# GPRSshield_v1_4_1.net
KiCad netlist of a schematic drawn in Altium Designer
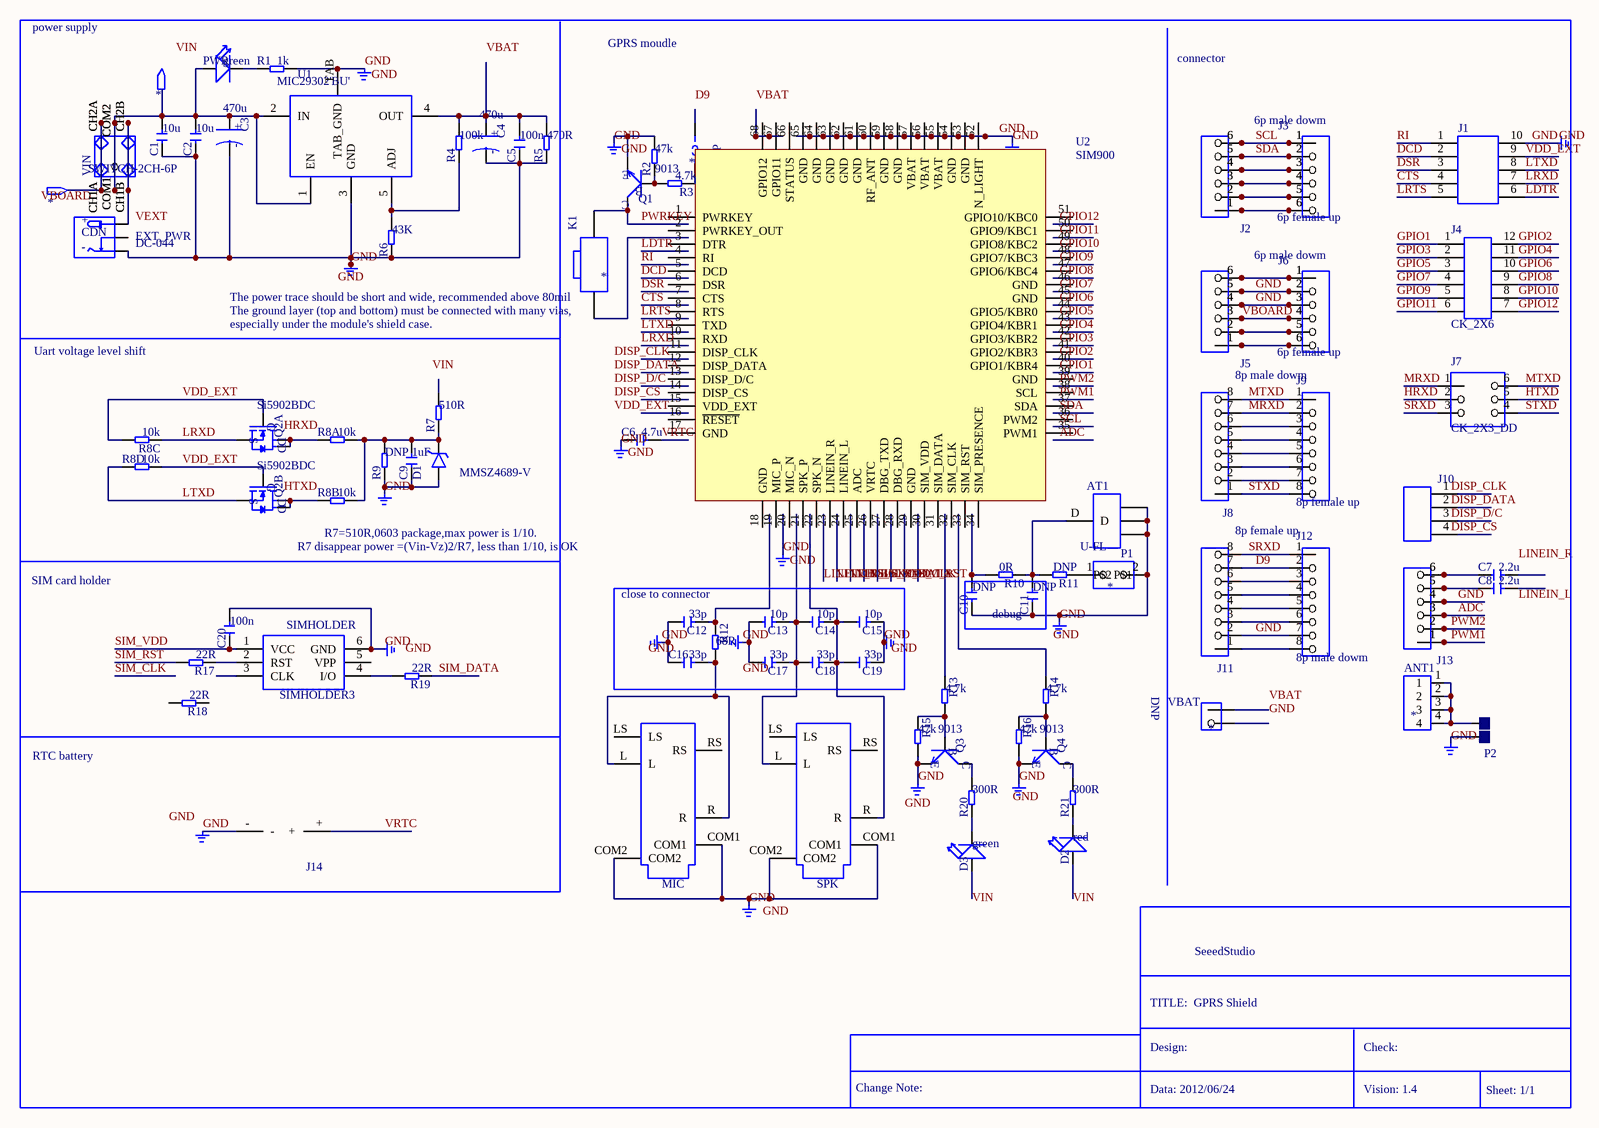
[diagram p0: GPRSshield v1.4_1.SchDoc]

(export (version "E")
  (design (tool "Eeschema 10.0.6"))
  (components
    (comp (ref "ANT1")
      (value "*")
      (footprint "SMA-TO-IPX")
      (libsource (lib "Connector") (part "ANTENNA-SMA-IPX"))
    )
    (comp (ref "AT1")
      (value "U-FL")
      (footprint "4P-U-FL")
      (libsource (lib "Connector") (part "ANTENNA-U-FL"))
    )
    (comp (ref "C1") (value "10u") (footprint "0603") (libsource (lib "Discrete") (part "C-0603")))
    (comp (ref "C2") (value "10u") (footprint "0603") (libsource (lib "Discrete") (part "C-0603")))
    (comp (ref "C3") (value "470u") (footprint "AVX_D") (libsource (lib "Discrete") (part "006-CAP_AVX_D")))
    (comp (ref "C4") (value "470u") (footprint "AVX_D") (libsource (lib "Discrete") (part "006-CAP_AVX_D")))
    (comp (ref "C5") (value "100n") (footprint "0603") (libsource (lib "Discrete") (part "C-0603")))
    (comp (ref "C6") (value "4.7u") (footprint "0805") (libsource (lib "Discrete") (part "C-0805")))
    (comp (ref "C7") (value "2.2u") (footprint "0603") (libsource (lib "Discrete") (part "C-0603")))
    (comp (ref "C8") (value "2.2u") (footprint "0603") (libsource (lib "Discrete") (part "C-0603")))
    (comp (ref "C9") (value "1uF") (footprint "0603") (libsource (lib "Discrete") (part "C-0603")))
    (comp (ref "C10") (value "DNP") (footprint "0402") (libsource (lib "") (part "C-0402_1")))
    (comp (ref "C11") (value "DNP") (footprint "0402") (libsource (lib "") (part "C-0402_1")))
    (comp (ref "C12") (value "33p") (footprint "0603") (libsource (lib "") (part "C-0603_1")))
    (comp (ref "C13") (value "10p") (footprint "0402") (libsource (lib "Discrete") (part "C-0402")))
    (comp (ref "C14") (value "10p") (footprint "0402") (libsource (lib "Discrete") (part "C-0402")))
    (comp (ref "C15") (value "10p") (footprint "0402") (libsource (lib "Discrete") (part "C-0402")))
    (comp (ref "C16") (value "33p") (footprint "0603") (libsource (lib "Discrete") (part "C-0603")))
    (comp (ref "C17") (value "33p") (footprint "0402") (libsource (lib "Discrete") (part "C-0402")))
    (comp (ref "C18") (value "33p") (footprint "0402") (libsource (lib "Discrete") (part "C-0402")))
    (comp (ref "C19") (value "33p") (footprint "0402") (libsource (lib "Discrete") (part "C-0402")))
    (comp (ref "C20") (value "100n") (footprint "0603") (libsource (lib "Discrete") (part "C-0603")))
    (comp (ref "D1")
      (value "MMSZ4689-V")
      (footprint "SOD123-2.7X1.6")
      (libsource (lib "template") (part "D-VOL'MMSZ4681'"))
    )
    (comp (ref "D2") (value "red") (footprint "LED-0603") (libsource (lib "Discrete") (part "LED'0603'")))
    (comp (ref "D3") (value "green") (footprint "LED-0603") (libsource (lib "Discrete") (part "LED'0603'")))
    (comp (ref "EXT_PWR") (value "DC-044") (footprint "DC-404") (libsource (lib "Connector") (part "DC-044")))
    (comp (ref "J1")
      (value "~")
      (footprint "2X5P-2.54")
      (libsource (lib "Connector") (part "HEADER-2X5P-2.54"))
    )
    (comp (ref "J2")
      (value "6p male dowm")
      (footprint "CK_1X6")
      (libsource (lib "CONNECTER") (part "HEADER_1X6"))
    )
    (comp (ref "J3")
      (value "6p female up")
      (footprint "CK_1X6")
      (libsource (lib "CONNECTER") (part "HEADER_1X6"))
    )
    (comp (ref "J4") (value "CK_2X6") (footprint "CK_2X6") (libsource (lib "CONNECTER") (part "CK_2X6")))
    (comp (ref "J5")
      (value "6p male dowm")
      (footprint "CK_1X6")
      (libsource (lib "CONNECTER") (part "HEADER_1X6"))
    )
    (comp (ref "J6")
      (value "6p female up")
      (footprint "CK_1X6")
      (libsource (lib "CONNECTER") (part "HEADER_1X6"))
    )
    (comp (ref "J7")
      (value "CK_2X3_DD")
      (footprint "CK_2X3")
      (libsource (lib "CONNECTER") (part "CK_2X3_DD"))
    )
    (comp (ref "J8")
      (value "8p male dowm")
      (footprint "CK_1X8")
      (libsource (lib "CONNECTER") (part "CK_1X8DD"))
    )
    (comp (ref "J9")
      (value "8p female up")
      (footprint "CK_1X8")
      (libsource (lib "CONNECTER") (part "CK_1X8DD"))
    )
    (comp (ref "J10")
      (value "~")
      (footprint "4P-2.54-90D-FEMALE")
      (libsource (lib "Connector") (part "HEADER-4P'2.54-90D-FEMALE'"))
    )
    (comp (ref "J11")
      (value "8p female up")
      (footprint "CK_1X8")
      (libsource (lib "CONNECTER") (part "CK_1X8DD"))
    )
    (comp (ref "J12")
      (value "8p male dowm")
      (footprint "CK_1X8")
      (libsource (lib "CONNECTER") (part "CK_1X8DD"))
    )
    (comp (ref "J13") (value "~") (footprint "CK_1X6") (libsource (lib "CONNECTER") (part "HEADER_1X6")))
    (comp (ref "J14")
      (value "~")
      (footprint "CR1220")
      (libsource (lib "Connector") (part "HOLDER-BATTERY-2P-CR1220"))
    )
    (comp (ref "JP")
      (value "*")
      (footprint "2P-SMD-3.3X2")
      (libsource (lib "Discrete") (part "PAD-SOLDERJUMPERNC"))
    )
    (comp (ref "K1") (value "*") (footprint "BTN_5.0_RST") (libsource (lib "CPT_SMD") (part "BOTTON_1_DP")))
    (comp (ref "MIC") (value "~") (footprint "3.5-SMD") (libsource (lib "Connector") (part "AUDIO-SMT")))
    (comp (ref "P1") (value "*") (footprint "JP") (libsource (lib "mySeeed") (part "JP")))
    (comp (ref "P2")
      (value "*")
      (footprint "2P-SMD-1.78X1.27")
      (libsource (lib "Discrete") (part "PAD-JUMPER-2P"))
    )
    (comp (ref "PWR") (value "green") (footprint "D0603") (libsource (lib "Discrete") (part "007-LED0603")))
    (comp (ref "Q1")
      (value "9013")
      (footprint "SOT23")
      (libsource (lib "Discrete") (part "TRANSISTOR-NPN-SOT23"))
    )
    (comp (ref "Q2")
      (value "Si5902BDC")
      (footprint "1206-8")
      (libsource (lib "Discrete") (part "010-DUAL-N-MOSFET_1206-8"))
    )
    (comp (ref "Q3") (value "9013") (footprint "SOT23") (libsource (lib "") (part "TRANSISTOR-NPN-SOT23_1")))
    (comp (ref "Q4") (value "9013") (footprint "SOT23") (libsource (lib "") (part "TRANSISTOR-NPN-SOT23_1")))
    (comp (ref "R1") (value "1k") (footprint "0603") (libsource (lib "Discrete") (part "R-0603")))
    (comp (ref "R2") (value "47k") (footprint "0603") (libsource (lib "Discrete") (part "R-0603")))
    (comp (ref "R3") (value "4.7k") (footprint "0603") (libsource (lib "Discrete") (part "R-0603")))
    (comp (ref "R4") (value "100k") (footprint "0603") (libsource (lib "Discrete") (part "R-0603")))
    (comp (ref "R5") (value "470R") (footprint "0603") (libsource (lib "Discrete") (part "R-0603")))
    (comp (ref "R6") (value "43K") (footprint "0603") (libsource (lib "Discrete") (part "R-0603")))
    (comp (ref "R7") (value "510R") (footprint "0603") (libsource (lib "Discrete") (part "R-0603")))
    (comp (ref "R8") (value "10k") (footprint "1206-8-3.3X2.4") (libsource (lib "") (part "R-4R-1206_2")))
    (comp (ref "R9") (value "DNP") (footprint "0603") (libsource (lib "Discrete") (part "R-0603")))
    (comp (ref "R10") (value "0R") (footprint "0402") (libsource (lib "Discrete") (part "R-0402")))
    (comp (ref "R11") (value "DNP") (footprint "0402") (libsource (lib "Discrete") (part "R-0402")))
    (comp (ref "R12") (value "68R") (footprint "0603") (libsource (lib "Discrete") (part "R-0603")))
    (comp (ref "R13") (value "4.7k") (footprint "0603") (libsource (lib "Discrete") (part "R-0603")))
    (comp (ref "R14") (value "4.7k") (footprint "0603") (libsource (lib "Discrete") (part "R-0603")))
    (comp (ref "R15") (value "47k") (footprint "0603") (libsource (lib "Discrete") (part "R-0603")))
    (comp (ref "R16") (value "47k") (footprint "0603") (libsource (lib "Discrete") (part "R-0603")))
    (comp (ref "R17") (value "22R") (footprint "0603") (libsource (lib "Discrete") (part "R-0603")))
    (comp (ref "R18") (value "22R") (footprint "0603") (libsource (lib "Discrete") (part "R-0603")))
    (comp (ref "R19") (value "22R") (footprint "0603") (libsource (lib "Discrete") (part "R-0603")))
    (comp (ref "R20") (value "300R") (footprint "0603") (libsource (lib "Discrete") (part "R-0603")))
    (comp (ref "R21") (value "300R") (footprint "0603") (libsource (lib "Discrete") (part "R-0603")))
    (comp (ref "SIMHOLDER")
      (value "SIMHOLDER3")
      (footprint "SIMHOLDER3")
      (libsource (lib "SparkFun2") (part "SIMHOLDER3"))
    )
    (comp (ref "SPK") (value "~") (footprint "3.5-SMD") (libsource (lib "Connector") (part "AUDIO-SMT")))
    (comp (ref "U$1") (value "*") (libsource (lib "") (part "SINGLE-PIN_1")))
    (comp (ref "U$2") (value "~") (libsource (lib "Power or GND") (part "GND_POWER")))
    (comp (ref "U$3") (value "~") (libsource (lib "") (part "GND_POWER_1")))
    (comp (ref "U$4") (value "~") (libsource (lib "Power or GND") (part "GND_POWER")))
    (comp (ref "U$5") (value "~") (libsource (lib "Power or GND") (part "GND_POWER")))
    (comp (ref "U$6") (value "~") (libsource (lib "Power or GND") (part "GND_POWER")))
    (comp (ref "U$7") (value "~") (libsource (lib "Power or GND") (part "GND_POWER")))
    (comp (ref "U$8") (value "~") (libsource (lib "") (part "GND_POWER_1")))
    (comp (ref "U$12") (value "~") (libsource (lib "Power or GND") (part "GND_POWER")))
    (comp (ref "U$13") (value "~") (libsource (lib "Power or GND") (part "GND_POWER")))
    (comp (ref "U$14") (value "~") (libsource (lib "") (part "GND_POWER_2")))
    (comp (ref "U$15") (value "~") (libsource (lib "") (part "GND_POWER_1")))
    (comp (ref "U$16") (value "~") (libsource (lib "Power or GND") (part "GND_POWER")))
    (comp (ref "U$17") (value "~") (libsource (lib "Power or GND") (part "GND_POWER")))
    (comp (ref "U$18") (value "~") (libsource (lib "Power or GND") (part "GND_POWER")))
    (comp (ref "U$19") (value "~") (libsource (lib "Power or GND") (part "GND_POWER")))
    (comp (ref "U$20") (value "~") (libsource (lib "") (part "GND_POWER_2")))
    (comp (ref "U$21") (value "~") (libsource (lib "Power or GND") (part "GND_POWER")))
    (comp (ref "U$22") (value "~") (libsource (lib "Power or GND") (part "GND_POWER")))
    (comp (ref "U$23") (value "*") (libsource (lib "Power or GND") (part "SINGLE-PIN")))
    (comp (ref "U1")
      (value "MIC29302'BU'")
      (footprint "TO-263")
      (libsource (lib "ICs_v54") (part "MIC29302'BU'"))
    )
    (comp (ref "U2") (value "SIM900") (footprint "SIM900") (libsource (lib "SIM900") (part "SIM900")))
    (comp (ref "VBAT")
      (value "*")
      (footprint "CK_1*2")
      (libsource (lib "CONNECTER") (part "HEADER_1X2_2.54"))
    )
    (comp (ref "VIN")
      (value "SWITCH-2CH-6P")
      (footprint "6P-2CH-2.54-7.6X3.0")
      (libsource (lib "Discrete") (part "SWITCH-2CH-6P"))
    )
  )
  (nets
    (net (code "1") (name "/ADC") (class "Default")
      (node (ref "J13") (pin "3") (pinfunction "3_3") (pintype "passive"))
    )
    (net (code "2") (name "/CTS") (class "Default")
      (node (ref "J1") (pin "4") (pinfunction "4_4") (pintype "passive"))
    )
    (net (code "3") (name "/D9") (class "Default")
      (node (ref "J11") (pin "7") (pinfunction "P$7_7") (pintype "passive"))
      (node (ref "J12") (pin "2") (pinfunction "P$2_2") (pintype "passive"))
    )
    (net (code "4") (name "/DCD") (class "Default")
      (node (ref "J1") (pin "2") (pinfunction "2_2") (pintype "passive"))
    )
    (net (code "9") (name "/DSR") (class "Default")
      (node (ref "J1") (pin "3") (pinfunction "3_3") (pintype "passive"))
    )
    (net (code "10") (name "/GND") (class "Default")
      (node (ref "AT1") (pin "GND1") (pinfunction "GND1_GND1") (pintype "passive"))
      (node (ref "AT1") (pin "GND2") (pinfunction "GND2_GND2") (pintype "passive"))
      (node (ref "AT1") (pin "GND3") (pinfunction "GND3_GND3") (pintype "passive"))
      (node (ref "C1") (pin "1") (pinfunction "1_1") (pintype "passive"))
      (node (ref "C10") (pin "1") (pinfunction "1_1") (pintype "passive"))
      (node (ref "C11") (pin "1") (pinfunction "1_1") (pintype "passive"))
      (node (ref "C12") (pin "2") (pinfunction "2_2") (pintype "passive"))
      (node (ref "C13") (pin "2") (pinfunction "2_2") (pintype "passive"))
      (node (ref "C15") (pin "1") (pinfunction "1_1") (pintype "passive"))
      (node (ref "C16") (pin "1") (pinfunction "1_1") (pintype "passive"))
      (node (ref "C17") (pin "2") (pinfunction "2_2") (pintype "passive"))
      (node (ref "C19") (pin "1") (pinfunction "1_1") (pintype "passive"))
      (node (ref "C2") (pin "1") (pinfunction "1_1") (pintype "passive"))
      (node (ref "C20") (pin "2") (pinfunction "2_2") (pintype "passive"))
      (node (ref "C3") (pin "-") (pinfunction "-_-") (pintype "passive"))
      (node (ref "C4") (pin "-") (pinfunction "-_-") (pintype "passive"))
      (node (ref "C5") (pin "1") (pinfunction "1_1") (pintype "passive"))
      (node (ref "C6") (pin "1") (pinfunction "1_1") (pintype "passive"))
      (node (ref "C9") (pin "1") (pinfunction "1_1") (pintype "passive"))
      (node (ref "D1") (pin "1") (pinfunction "1_1") (pintype "passive"))
      (node (ref "EXT_PWR") (pin "-") (pinfunction "-_-") (pintype "passive"))
      (node (ref "J1") (pin "10") (pinfunction "10_10") (pintype "passive"))
      (node (ref "J11") (pin "2") (pinfunction "P$2_2") (pintype "passive"))
      (node (ref "J12") (pin "7") (pinfunction "P$7_7") (pintype "passive"))
      (node (ref "J13") (pin "4") (pinfunction "4_4") (pintype "passive"))
      (node (ref "J14") (pin "-") (pinfunction "-_-") (pintype "passive"))
      (node (ref "J5") (pin "4") (pinfunction "4_4") (pintype "passive"))
      (node (ref "J5") (pin "5") (pinfunction "5_5") (pintype "passive"))
      (node (ref "J6") (pin "2") (pinfunction "2_2") (pintype "passive"))
      (node (ref "J6") (pin "3") (pinfunction "3_3") (pintype "passive"))
      (node (ref "MIC") (pin "COM1") (pinfunction "COM1_COM1") (pintype "passive"))
      (node (ref "MIC") (pin "COM2") (pinfunction "COM2_COM2") (pintype "passive"))
      (node (ref "P1") (pin "2") (pinfunction "P$2_2") (pintype "passive"))
      (node (ref "P2") (pin "2") (pinfunction "2_2") (pintype "passive"))
      (node (ref "Q1") (pin "2") (pinfunction "E_2") (pintype "passive"))
      (node (ref "Q3") (pin "2") (pinfunction "E_2") (pintype "passive"))
      (node (ref "Q4") (pin "2") (pinfunction "E_2") (pintype "passive"))
      (node (ref "R1") (pin "2") (pinfunction "2_2") (pintype "passive"))
      (node (ref "R15") (pin "2") (pinfunction "2_2") (pintype "passive"))
      (node (ref "R16") (pin "2") (pinfunction "2_2") (pintype "passive"))
      (node (ref "R2") (pin "2") (pinfunction "2_2") (pintype "passive"))
      (node (ref "R5") (pin "1") (pinfunction "1_1") (pintype "passive"))
      (node (ref "R6") (pin "1") (pinfunction "1_1") (pintype "passive"))
      (node (ref "R9") (pin "1") (pinfunction "1_1") (pintype "passive"))
      (node (ref "SIMHOLDER") (pin "6") (pinfunction "GND_6") (pintype "passive"))
      (node (ref "SPK") (pin "COM1") (pinfunction "COM1_COM1") (pintype "passive"))
      (node (ref "SPK") (pin "COM2") (pinfunction "COM2_COM2") (pintype "passive"))
      (node (ref "U$12") (pin "0") (pinfunction "GND_0") (pintype "passive"))
      (node (ref "U$13") (pin "0") (pinfunction "GND_0") (pintype "passive"))
      (node (ref "U$14") (pin "0") (pinfunction "GND_0") (pintype "passive"))
      (node (ref "U$15") (pin "0") (pinfunction "GND_0") (pintype "passive"))
      (node (ref "U$16") (pin "0") (pinfunction "GND_0") (pintype "passive"))
      (node (ref "U$17") (pin "0") (pinfunction "GND_0") (pintype "passive"))
      (node (ref "U$18") (pin "0") (pinfunction "GND_0") (pintype "passive"))
      (node (ref "U$19") (pin "0") (pinfunction "GND_0") (pintype "passive"))
      (node (ref "U$2") (pin "0") (pinfunction "GND_0") (pintype "passive"))
      (node (ref "U$20") (pin "0") (pinfunction "GND_0") (pintype "passive"))
      (node (ref "U$21") (pin "0") (pinfunction "GND_0") (pintype "passive"))
      (node (ref "U$22") (pin "0") (pinfunction "GND_0") (pintype "passive"))
      (node (ref "U$3") (pin "0") (pinfunction "GND_0") (pintype "passive"))
      (node (ref "U$4") (pin "0") (pinfunction "GND_0") (pintype "passive"))
      (node (ref "U$5") (pin "0") (pinfunction "GND_0") (pintype "passive"))
      (node (ref "U$6") (pin "0") (pinfunction "GND_0") (pintype "passive"))
      (node (ref "U$7") (pin "0") (pinfunction "GND_0") (pintype "passive"))
      (node (ref "U$8") (pin "0") (pinfunction "GND_0") (pintype "passive"))
      (node (ref "U1") (pin "3") (pinfunction "GND_3") (pintype "passive"))
      (node (ref "U1") (pin "TAB") (pinfunction "TAB_GND_TAB") (pintype "passive"))
    )
    (net (code "11") (name "/GPIO1") (class "Default")
      (node (ref "J4") (pin "1") (pinfunction "1_1") (pintype "passive"))
    )
    (net (code "12") (name "/GPIO2") (class "Default")
      (node (ref "J4") (pin "12") (pinfunction "12_12") (pintype "passive"))
    )
    (net (code "13") (name "/GPIO3") (class "Default")
      (node (ref "J4") (pin "2") (pinfunction "2_2") (pintype "passive"))
    )
    (net (code "14") (name "/GPIO4") (class "Default")
      (node (ref "J4") (pin "11") (pinfunction "11_11") (pintype "passive"))
    )
    (net (code "15") (name "/GPIO5") (class "Default")
      (node (ref "J4") (pin "3") (pinfunction "3_3") (pintype "passive"))
    )
    (net (code "16") (name "/GPIO6") (class "Default")
      (node (ref "J4") (pin "10") (pinfunction "10_10") (pintype "passive"))
    )
    (net (code "17") (name "/GPIO7") (class "Default")
      (node (ref "J4") (pin "4") (pinfunction "4_4") (pintype "passive"))
    )
    (net (code "18") (name "/GPIO8") (class "Default")
      (node (ref "J4") (pin "9") (pinfunction "9_9") (pintype "passive"))
    )
    (net (code "19") (name "/GPIO9") (class "Default")
      (node (ref "J4") (pin "5") (pinfunction "5_5") (pintype "passive"))
    )
    (net (code "20") (name "/GPIO10") (class "Default")
      (node (ref "J4") (pin "8") (pinfunction "8_8") (pintype "passive"))
    )
    (net (code "21") (name "/GPIO11") (class "Default")
      (node (ref "J4") (pin "6") (pinfunction "6_6") (pintype "passive"))
    )
    (net (code "22") (name "/GPIO12") (class "Default")
      (node (ref "J4") (pin "7") (pinfunction "7_7") (pintype "passive"))
    )
    (net (code "23") (name "/HRXD") (class "Default")
      (node (ref "J7") (pin "2") (pinfunction "2_2") (pintype "passive"))
    )
    (net (code "24") (name "/HTXD") (class "Default")
      (node (ref "J7") (pin "5") (pinfunction "5_5") (pintype "passive"))
    )
    (net (code "27") (name "/LDTR") (class "Default")
      (node (ref "J1") (pin "6") (pinfunction "6_6") (pintype "passive"))
    )
    (net (code "30") (name "/LRTS") (class "Default")
      (node (ref "J1") (pin "5") (pinfunction "5_5") (pintype "passive"))
    )
    (net (code "31") (name "/LRXD") (class "Default")
      (node (ref "J1") (pin "7") (pinfunction "7_7") (pintype "passive"))
      (node (ref "Q2") (pin "1") (pinfunction "S_1") (pintype "passive"))
      (node (ref "R8") (pin "3") (pinfunction "1_3") (pintype "passive"))
    )
    (net (code "32") (name "/LTXD") (class "Default")
      (node (ref "J1") (pin "8") (pinfunction "8_8") (pintype "passive"))
      (node (ref "Q2") (pin "3") (pinfunction "S_3") (pintype "passive"))
      (node (ref "R8") (pin "4") (pinfunction "1_4") (pintype "passive"))
    )
    (net (code "33") (name "/MRXD") (class "Default")
      (node (ref "J7") (pin "1") (pinfunction "1_1") (pintype "passive"))
      (node (ref "J8") (pin "7") (pinfunction "P$7_7") (pintype "passive"))
      (node (ref "J9") (pin "2") (pinfunction "P$2_2") (pintype "passive"))
    )
    (net (code "34") (name "/MTXD") (class "Default")
      (node (ref "J7") (pin "6") (pinfunction "6_6") (pintype "passive"))
      (node (ref "J8") (pin "8") (pinfunction "P$8_8") (pintype "passive"))
      (node (ref "J9") (pin "1") (pinfunction "P$1_1") (pintype "passive"))
    )
    (net (code "35") (name "/PWM1") (class "Default")
      (node (ref "J13") (pin "1") (pinfunction "1_1") (pintype "passive"))
    )
    (net (code "36") (name "/PWM2") (class "Default")
      (node (ref "J13") (pin "2") (pinfunction "2_2") (pintype "passive"))
    )
    (net (code "37") (name "/PWRKEY") (class "Default")
      (node (ref "K1") (pin "P$2") (pinfunction "2_P$2") (pintype "passive"))
      (node (ref "Q1") (pin "3") (pinfunction "C_3") (pintype "passive"))
    )
    (net (code "38") (name "/RI") (class "Default")
      (node (ref "J1") (pin "1") (pinfunction "1_1") (pintype "passive"))
    )
    (net (code "39") (name "/SCL") (class "Default")
      (node (ref "J2") (pin "6") (pinfunction "6_6") (pintype "passive"))
      (node (ref "J3") (pin "1") (pinfunction "1_1") (pintype "passive"))
    )
    (net (code "40") (name "/SDA") (class "Default")
      (node (ref "J2") (pin "5") (pinfunction "5_5") (pintype "passive"))
      (node (ref "J3") (pin "2") (pinfunction "2_2") (pintype "passive"))
    )
    (net (code "42") (name "/SIM_DATA") (class "Default")
      (node (ref "R19") (pin "1") (pinfunction "1_1") (pintype "passive"))
    )
    (net (code "43") (name "/SIM_RST") (class "Default")
      (node (ref "R17") (pin "2") (pinfunction "2_2") (pintype "passive"))
    )
    (net (code "44") (name "/SIM_VDD") (class "Default")
      (node (ref "C20") (pin "1") (pinfunction "1_1") (pintype "passive"))
      (node (ref "SIMHOLDER") (pin "1") (pinfunction "VCC_1") (pintype "passive"))
    )
    (net (code "45") (name "/SRXD") (class "Default")
      (node (ref "J11") (pin "8") (pinfunction "P$8_8") (pintype "passive"))
      (node (ref "J12") (pin "1") (pinfunction "P$1_1") (pintype "passive"))
      (node (ref "J7") (pin "3") (pinfunction "3_3") (pintype "passive"))
    )
    (net (code "46") (name "/STXD") (class "Default")
      (node (ref "J7") (pin "4") (pinfunction "4_4") (pintype "passive"))
      (node (ref "J8") (pin "1") (pinfunction "P$1_1") (pintype "passive"))
      (node (ref "J9") (pin "8") (pinfunction "P$8_8") (pintype "passive"))
    )
    (net (code "48") (name "/VBOARD") (class "Default")
      (node (ref "J5") (pin "3") (pinfunction "3_3") (pintype "passive"))
      (node (ref "J6") (pin "4") (pinfunction "4_4") (pintype "passive"))
    )
    (net (code "49") (name "/VDD_EXT") (class "Default")
      (node (ref "J1") (pin "9") (pinfunction "9_9") (pintype "passive"))
      (node (ref "Q2") (pin "2") (pinfunction "G_2") (pintype "passive"))
      (node (ref "Q2") (pin "4") (pinfunction "G_4") (pintype "passive"))
      (node (ref "R8") (pin "5") (pinfunction "2_5") (pintype "passive"))
      (node (ref "R8") (pin "6") (pinfunction "2_6") (pintype "passive"))
    )
    (net (code "52") (name "/VRTC") (class "Default")
      (node (ref "C6") (pin "2") (pinfunction "2_2") (pintype "passive"))
      (node (ref "J14") (pin "+") (pinfunction "+_+") (pintype "passive"))
    )
    (net (code "53") (name "Net-(ANT1-Pad1)") (class "Default")
      (node (ref "ANT1") (pin "1") (pinfunction "1_1") (pintype "passive"))
      (node (ref "ANT1") (pin "2") (pinfunction "2_2") (pintype "passive"))
      (node (ref "ANT1") (pin "3") (pinfunction "3_3") (pintype "passive"))
      (node (ref "ANT1") (pin "4") (pinfunction "4_4") (pintype "passive"))
      (node (ref "P2") (pin "1") (pinfunction "1_1") (pintype "passive"))
    )
    (net (code "54") (name "Net-(AT1-PadD)") (class "Default")
      (node (ref "AT1") (pin "D") (pinfunction "D_D") (pintype "passive"))
      (node (ref "C11") (pin "2") (pinfunction "2_2") (pintype "passive"))
      (node (ref "R10") (pin "1") (pinfunction "1_1") (pintype "passive"))
      (node (ref "R11") (pin "2") (pinfunction "2_2") (pintype "passive"))
    )
    (net (code "55") (name "Net-(C7-Pad1)") (class "Default")
      (node (ref "C7") (pin "1") (pinfunction "1_1") (pintype "passive"))
      (node (ref "J13") (pin "6") (pinfunction "6_6") (pintype "passive"))
    )
    (net (code "56") (name "Net-(C8-Pad1)") (class "Default")
      (node (ref "C8") (pin "1") (pinfunction "1_1") (pintype "passive"))
      (node (ref "J13") (pin "5") (pinfunction "5_5") (pintype "passive"))
    )
    (net (code "57") (name "Net-(C10-Pad2)") (class "Default")
      (node (ref "C10") (pin "2") (pinfunction "2_2") (pintype "passive"))
      (node (ref "R10") (pin "2") (pinfunction "2_2") (pintype "passive"))
    )
    (net (code "58") (name "Net-(C12-Pad1)") (class "Default")
      (node (ref "C12") (pin "1") (pinfunction "1_1") (pintype "passive"))
      (node (ref "R12") (pin "1") (pinfunction "1_1") (pintype "passive"))
    )
    (net (code "59") (name "Net-(C13-Pad1)") (class "Default")
      (node (ref "C13") (pin "1") (pinfunction "1_1") (pintype "passive"))
      (node (ref "C14") (pin "2") (pinfunction "2_2") (pintype "passive"))
      (node (ref "C17") (pin "1") (pinfunction "1_1") (pintype "passive"))
      (node (ref "C18") (pin "2") (pinfunction "2_2") (pintype "passive"))
      (node (ref "SPK") (pin "L") (pinfunction "L_L") (pintype "passive"))
    )
    (net (code "60") (name "Net-(C14-Pad1)") (class "Default")
      (node (ref "C14") (pin "1") (pinfunction "1_1") (pintype "passive"))
      (node (ref "C15") (pin "2") (pinfunction "2_2") (pintype "passive"))
      (node (ref "C18") (pin "1") (pinfunction "1_1") (pintype "passive"))
      (node (ref "C19") (pin "2") (pinfunction "2_2") (pintype "passive"))
      (node (ref "SPK") (pin "R") (pinfunction "R_R") (pintype "passive"))
    )
    (net (code "61") (name "Net-(C16-Pad2)") (class "Default")
      (node (ref "C16") (pin "2") (pinfunction "2_2") (pintype "passive"))
      (node (ref "MIC") (pin "L") (pinfunction "L_L") (pintype "passive"))
      (node (ref "MIC") (pin "R") (pinfunction "R_R") (pintype "passive"))
      (node (ref "R12") (pin "2") (pinfunction "2_2") (pintype "passive"))
    )
    (net (code "62") (name "Net-(D2-Pad-)") (class "Default")
      (node (ref "D2") (pin "-") (pinfunction "-_-") (pintype "passive"))
      (node (ref "R21") (pin "1") (pinfunction "1_1") (pintype "passive"))
    )
    (net (code "63") (name "Net-(D3-Pad-)") (class "Default")
      (node (ref "D3") (pin "-") (pinfunction "-_-") (pintype "passive"))
      (node (ref "R20") (pin "1") (pinfunction "1_1") (pintype "passive"))
    )
    (net (code "64") (name "Net-(EXT_PWR-Pad+)") (class "Default")
      (node (ref "EXT_PWR") (pin "+") (pinfunction "+_+") (pintype "passive"))
      (node (ref "VIN") (pin "CH1B") (pinfunction "CH1B_CH1B") (pintype "passive"))
      (node (ref "VIN") (pin "CH2B") (pinfunction "CH2B_CH2B") (pintype "passive"))
    )
    (net (code "65") (name "Net-(J2-Pad1)") (class "Default")
      (node (ref "J2") (pin "1") (pinfunction "1_1") (pintype "passive"))
      (node (ref "J3") (pin "6") (pinfunction "6_6") (pintype "passive"))
    )
    (net (code "66") (name "Net-(J2-Pad2)") (class "Default")
      (node (ref "J2") (pin "2") (pinfunction "2_2") (pintype "passive"))
      (node (ref "J3") (pin "5") (pinfunction "5_5") (pintype "passive"))
    )
    (net (code "67") (name "Net-(J2-Pad3)") (class "Default")
      (node (ref "J2") (pin "3") (pinfunction "3_3") (pintype "passive"))
      (node (ref "J3") (pin "4") (pinfunction "4_4") (pintype "passive"))
    )
    (net (code "68") (name "Net-(J2-Pad4)") (class "Default")
      (node (ref "J2") (pin "4") (pinfunction "4_4") (pintype "passive"))
      (node (ref "J3") (pin "3") (pinfunction "3_3") (pintype "passive"))
    )
    (net (code "69") (name "Net-(J5-Pad1)") (class "Default")
      (node (ref "J5") (pin "1") (pinfunction "1_1") (pintype "passive"))
      (node (ref "J6") (pin "6") (pinfunction "6_6") (pintype "passive"))
    )
    (net (code "70") (name "Net-(J5-Pad2)") (class "Default")
      (node (ref "J5") (pin "2") (pinfunction "2_2") (pintype "passive"))
      (node (ref "J6") (pin "5") (pinfunction "5_5") (pintype "passive"))
    )
    (net (code "71") (name "Net-(J5-Pad6)") (class "Default")
      (node (ref "J5") (pin "6") (pinfunction "6_6") (pintype "passive"))
      (node (ref "J6") (pin "1") (pinfunction "1_1") (pintype "passive"))
    )
    (net (code "72") (name "Net-(J8-P$2)") (class "Default")
      (node (ref "J8") (pin "2") (pinfunction "P$2_2") (pintype "passive"))
      (node (ref "J9") (pin "7") (pinfunction "P$7_7") (pintype "passive"))
    )
    (net (code "73") (name "Net-(J8-P$3)") (class "Default")
      (node (ref "J8") (pin "3") (pinfunction "P$3_3") (pintype "passive"))
      (node (ref "J9") (pin "6") (pinfunction "P$6_6") (pintype "passive"))
    )
    (net (code "74") (name "Net-(J8-P$4)") (class "Default")
      (node (ref "J8") (pin "4") (pinfunction "P$4_4") (pintype "passive"))
      (node (ref "J9") (pin "5") (pinfunction "P$5_5") (pintype "passive"))
    )
    (net (code "75") (name "Net-(J8-P$5)") (class "Default")
      (node (ref "J8") (pin "5") (pinfunction "P$5_5") (pintype "passive"))
      (node (ref "J9") (pin "4") (pinfunction "P$4_4") (pintype "passive"))
    )
    (net (code "76") (name "Net-(J8-P$6)") (class "Default")
      (node (ref "J8") (pin "6") (pinfunction "P$6_6") (pintype "passive"))
      (node (ref "J9") (pin "3") (pinfunction "P$3_3") (pintype "passive"))
    )
    (net (code "77") (name "Net-(J11-P$1)") (class "Default")
      (node (ref "J11") (pin "1") (pinfunction "P$1_1") (pintype "passive"))
      (node (ref "J12") (pin "8") (pinfunction "P$8_8") (pintype "passive"))
    )
    (net (code "78") (name "Net-(J11-P$3)") (class "Default")
      (node (ref "J11") (pin "3") (pinfunction "P$3_3") (pintype "passive"))
      (node (ref "J12") (pin "6") (pinfunction "P$6_6") (pintype "passive"))
    )
    (net (code "79") (name "Net-(J11-P$4)") (class "Default")
      (node (ref "J11") (pin "4") (pinfunction "P$4_4") (pintype "passive"))
      (node (ref "J12") (pin "5") (pinfunction "P$5_5") (pintype "passive"))
    )
    (net (code "80") (name "Net-(J11-P$5)") (class "Default")
      (node (ref "J11") (pin "5") (pinfunction "P$5_5") (pintype "passive"))
      (node (ref "J12") (pin "4") (pinfunction "P$4_4") (pintype "passive"))
    )
    (net (code "81") (name "Net-(J11-P$6)") (class "Default")
      (node (ref "J11") (pin "6") (pinfunction "P$6_6") (pintype "passive"))
      (node (ref "J12") (pin "3") (pinfunction "P$3_3") (pintype "passive"))
    )
    (net (code "82") (name "Net-(JP-Pad2)") (class "Default")
      (node (ref "JP") (pin "2") (pinfunction "2_2") (pintype "passive"))
      (node (ref "R3") (pin "1") (pinfunction "1_1") (pintype "passive"))
    )
    (net (code "83") (name "Net-(P1-P$1)") (class "Default")
      (node (ref "P1") (pin "1") (pinfunction "P$1_1") (pintype "passive"))
      (node (ref "R11") (pin "1") (pinfunction "1_1") (pintype "passive"))
    )
    (net (code "84") (name "Net-(PWR-Pad-)") (class "Default")
      (node (ref "PWR") (pin "-") (pinfunction "-_-") (pintype "passive"))
      (node (ref "R1") (pin "1") (pinfunction "1_1") (pintype "passive"))
    )
    (net (code "85") (name "Net-(Q1-B)") (class "Default")
      (node (ref "Q1") (pin "1") (pinfunction "B_1") (pintype "passive"))
      (node (ref "R2") (pin "1") (pinfunction "1_1") (pintype "passive"))
      (node (ref "R3") (pin "2") (pinfunction "2_2") (pintype "passive"))
    )
    (net (code "86") (name "Net-(Q2A-D@1)") (class "Default")
      (node (ref "Q2") (pin "7") (pinfunction "D@1_7") (pintype "passive"))
      (node (ref "Q2") (pin "8") (pinfunction "D@2_8") (pintype "passive"))
      (node (ref "R8") (pin "1") (pinfunction "1_1") (pintype "passive"))
    )
    (net (code "87") (name "Net-(Q2B-D@1)") (class "Default")
      (node (ref "Q2") (pin "5") (pinfunction "D@1_5") (pintype "passive"))
      (node (ref "Q2") (pin "6") (pinfunction "D@2_6") (pintype "passive"))
      (node (ref "R8") (pin "2") (pinfunction "1_2") (pintype "passive"))
    )
    (net (code "88") (name "Net-(Q3-B)") (class "Default")
      (node (ref "Q3") (pin "1") (pinfunction "B_1") (pintype "passive"))
      (node (ref "R13") (pin "2") (pinfunction "2_2") (pintype "passive"))
      (node (ref "R15") (pin "1") (pinfunction "1_1") (pintype "passive"))
    )
    (net (code "89") (name "Net-(Q3-C)") (class "Default")
      (node (ref "Q3") (pin "3") (pinfunction "C_3") (pintype "passive"))
      (node (ref "R20") (pin "2") (pinfunction "2_2") (pintype "passive"))
    )
    (net (code "90") (name "Net-(Q4-B)") (class "Default")
      (node (ref "Q4") (pin "1") (pinfunction "B_1") (pintype "passive"))
      (node (ref "R14") (pin "2") (pinfunction "2_2") (pintype "passive"))
      (node (ref "R16") (pin "1") (pinfunction "1_1") (pintype "passive"))
    )
    (net (code "91") (name "Net-(Q4-C)") (class "Default")
      (node (ref "Q4") (pin "3") (pinfunction "C_3") (pintype "passive"))
      (node (ref "R21") (pin "2") (pinfunction "2_2") (pintype "passive"))
    )
    (net (code "92") (name "Net-(R8A-2)") (class "Default")
      (node (ref "C9") (pin "2") (pinfunction "2_2") (pintype "passive"))
      (node (ref "D1") (pin "2") (pinfunction "2_2") (pintype "passive"))
      (node (ref "R7") (pin "1") (pinfunction "1_1") (pintype "passive"))
      (node (ref "R8") (pin "7") (pinfunction "2_7") (pintype "passive"))
      (node (ref "R8") (pin "8") (pinfunction "2_8") (pintype "passive"))
      (node (ref "R9") (pin "2") (pinfunction "2_2") (pintype "passive"))
    )
    (net (code "93") (name "Net-(SIMHOLDER-I{slash}O)") (class "Default")
      (node (ref "R19") (pin "2") (pinfunction "2_2") (pintype "passive"))
      (node (ref "SIMHOLDER") (pin "4") (pinfunction "I/O_4") (pintype "passive"))
    )
    (net (code "94") (name "Net-(SIMHOLDER-RST)") (class "Default")
      (node (ref "R17") (pin "1") (pinfunction "1_1") (pintype "passive"))
      (node (ref "SIMHOLDER") (pin "2") (pinfunction "RST_2") (pintype "passive"))
    )
    (net (code "95") (name "Net-(U1-ADJ)") (class "Default")
      (node (ref "R4") (pin "1") (pinfunction "1_1") (pintype "passive"))
      (node (ref "R6") (pin "2") (pinfunction "2_2") (pintype "passive"))
      (node (ref "U1") (pin "5") (pinfunction "ADJ_5") (pintype "passive"))
    )
    (net (code "96") (name "Net-(U1-EN)") (class "Default")
      (node (ref "C1") (pin "2") (pinfunction "2_2") (pintype "passive"))
      (node (ref "C2") (pin "2") (pinfunction "2_2") (pintype "passive"))
      (node (ref "C3") (pin "+") (pinfunction "+_+") (pintype "passive"))
      (node (ref "PWR") (pin "+") (pinfunction "+_+") (pintype "passive"))
      (node (ref "U1") (pin "1") (pinfunction "EN_1") (pintype "passive"))
      (node (ref "U1") (pin "2") (pinfunction "IN_2") (pintype "passive"))
      (node (ref "VIN") (pin "COM1") (pinfunction "COM1_COM1") (pintype "passive"))
      (node (ref "VIN") (pin "COM2") (pinfunction "COM2_COM2") (pintype "passive"))
    )
    (net (code "97") (name "Net-(U1-OUT)") (class "Default")
      (node (ref "C4") (pin "+") (pinfunction "+_+") (pintype "passive"))
      (node (ref "C5") (pin "2") (pinfunction "2_2") (pintype "passive"))
      (node (ref "R4") (pin "2") (pinfunction "2_2") (pintype "passive"))
      (node (ref "R5") (pin "2") (pinfunction "2_2") (pintype "passive"))
      (node (ref "U1") (pin "4") (pinfunction "OUT_4") (pintype "passive"))
    )
    (net (code "98") (name "Net-(VIN-PadCH1A)") (class "Default")
      (node (ref "VIN") (pin "CH1A") (pinfunction "CH1A_CH1A") (pintype "passive"))
      (node (ref "VIN") (pin "CH2A") (pinfunction "CH2A_CH2A") (pintype "passive"))
    )
    (net (code "99") (name "unconnected-(C7-Pad2)") (class "Default")
      (node (ref "C7") (pin "2") (pinfunction "2_2") (pintype "passive"))
    )
    (net (code "100") (name "unconnected-(C8-Pad2)") (class "Default")
      (node (ref "C8") (pin "2") (pinfunction "2_2") (pintype "passive"))
    )
    (net (code "101") (name "unconnected-(D2-Pad+)") (class "Default")
      (node (ref "D2") (pin "+") (pinfunction "+_+") (pintype "passive"))
    )
    (net (code "102") (name "unconnected-(D3-Pad+)") (class "Default")
      (node (ref "D3") (pin "+") (pinfunction "+_+") (pintype "passive"))
    )
    (net (code "103") (name "unconnected-(EXT_PWR-PadCDN)") (class "Default")
      (node (ref "EXT_PWR") (pin "CDN") (pinfunction "CDN_CDN") (pintype "passive"))
    )
    (net (code "104") (name "unconnected-(J10-P$1-Pad1)") (class "Default")
      (node (ref "J10") (pin "1") (pinfunction "P$1_1") (pintype "passive"))
    )
    (net (code "105") (name "unconnected-(J10-P$2-Pad2)") (class "Default")
      (node (ref "J10") (pin "2") (pinfunction "P$2_2") (pintype "passive"))
    )
    (net (code "106") (name "unconnected-(J10-P$3-Pad3)") (class "Default")
      (node (ref "J10") (pin "3") (pinfunction "P$3_3") (pintype "passive"))
    )
    (net (code "107") (name "unconnected-(J10-P$4-Pad4)") (class "Default")
      (node (ref "J10") (pin "4") (pinfunction "P$4_4") (pintype "passive"))
    )
    (net (code "108") (name "unconnected-(JP-Pad1)") (class "Default")
      (node (ref "JP") (pin "1") (pinfunction "1_1") (pintype "passive"))
    )
    (net (code "109") (name "unconnected-(K1-1-PadP$1)") (class "Default")
      (node (ref "K1") (pin "P$1") (pinfunction "1_P$1") (pintype "passive"))
    )
    (net (code "110") (name "unconnected-(MIC-PadLS)") (class "Default")
      (node (ref "MIC") (pin "LS") (pinfunction "LS_LS") (pintype "passive"))
    )
    (net (code "111") (name "unconnected-(MIC-PadRS)") (class "Default")
      (node (ref "MIC") (pin "RS") (pinfunction "RS_RS") (pintype "passive"))
    )
    (net (code "112") (name "unconnected-(R7-Pad2)") (class "Default")
      (node (ref "R7") (pin "2") (pinfunction "2_2") (pintype "passive"))
    )
    (net (code "113") (name "unconnected-(R13-Pad1)") (class "Default")
      (node (ref "R13") (pin "1") (pinfunction "1_1") (pintype "passive"))
    )
    (net (code "114") (name "unconnected-(R14-Pad1)") (class "Default")
      (node (ref "R14") (pin "1") (pinfunction "1_1") (pintype "passive"))
    )
    (net (code "115") (name "unconnected-(R18-Pad1)") (class "Default")
      (node (ref "R18") (pin "1") (pinfunction "1_1") (pintype "passive"))
    )
    (net (code "116") (name "unconnected-(R18-Pad2)") (class "Default")
      (node (ref "R18") (pin "2") (pinfunction "2_2") (pintype "passive"))
    )
    (net (code "117") (name "unconnected-(SIMHOLDER-CLK-Pad3)") (class "Default")
      (node (ref "SIMHOLDER") (pin "3") (pinfunction "CLK_3") (pintype "passive"))
    )
    (net (code "118") (name "unconnected-(SIMHOLDER-VPP-Pad5)") (class "Default")
      (node (ref "SIMHOLDER") (pin "5") (pinfunction "VPP_5") (pintype "passive"))
    )
    (net (code "119") (name "unconnected-(SPK-PadLS)") (class "Default")
      (node (ref "SPK") (pin "LS") (pinfunction "LS_LS") (pintype "passive"))
    )
    (net (code "120") (name "unconnected-(SPK-PadRS)") (class "Default")
      (node (ref "SPK") (pin "RS") (pinfunction "RS_RS") (pintype "passive"))
    )
    (net (code "121") (name "unconnected-(U2-ADC-Pad25)") (class "Default")
      (node (ref "U2") (pin "25") (pinfunction "ADC_25") (pintype "passive"))
    )
    (net (code "122") (name "unconnected-(U2-CTS-Pad7)") (class "Default")
      (node (ref "U2") (pin "7") (pinfunction "CTS_7") (pintype "passive"))
    )
    (net (code "123") (name "unconnected-(U2-DBG_RXD-Pad28)") (class "Default")
      (node (ref "U2") (pin "28") (pinfunction "DBG_RXD_28") (pintype "passive"))
    )
    (net (code "124") (name "unconnected-(U2-DBG_TXD-Pad27)") (class "Default")
      (node (ref "U2") (pin "27") (pinfunction "DBG_TXD_27") (pintype "passive"))
    )
    (net (code "125") (name "unconnected-(U2-DCD-Pad5)") (class "Default")
      (node (ref "U2") (pin "5") (pinfunction "DCD_5") (pintype "passive"))
    )
    (net (code "126") (name "unconnected-(U2-DISP_CLK-Pad11)") (class "Default")
      (node (ref "U2") (pin "11") (pinfunction "DISP_CLK_11") (pintype "passive"))
    )
    (net (code "127") (name "unconnected-(U2-DISP_CS-Pad14)") (class "Default")
      (node (ref "U2") (pin "14") (pinfunction "DISP_CS_14") (pintype "passive"))
    )
    (net (code "128") (name "unconnected-(U2-DISP_DATA-Pad12)") (class "Default")
      (node (ref "U2") (pin "12") (pinfunction "DISP_DATA_12") (pintype "passive"))
    )
    (net (code "129") (name "unconnected-(U2-DISP_D{slash}C-Pad13)") (class "Default")
      (node (ref "U2") (pin "13") (pinfunction "DISP_D/C_13") (pintype "passive"))
    )
    (net (code "130") (name "unconnected-(U2-DSR-Pad6)") (class "Default")
      (node (ref "U2") (pin "6") (pinfunction "DSR_6") (pintype "passive"))
    )
    (net (code "131") (name "unconnected-(U2-DTR-Pad3)") (class "Default")
      (node (ref "U2") (pin "3") (pinfunction "DTR_3") (pintype "passive"))
    )
    (net (code "132") (name "unconnected-(U2-GND-Pad17)") (class "Default")
      (node (ref "U2") (pin "17") (pinfunction "GND_17") (pintype "passive"))
    )
    (net (code "133") (name "unconnected-(U2-GND-Pad18)") (class "Default")
      (node (ref "U2") (pin "18") (pinfunction "GND_18") (pintype "passive"))
    )
    (net (code "134") (name "unconnected-(U2-GND-Pad29)") (class "Default")
      (node (ref "U2") (pin "29") (pinfunction "GND_29") (pintype "passive"))
    )
    (net (code "135") (name "unconnected-(U2-GND-Pad39)") (class "Default")
      (node (ref "U2") (pin "39") (pinfunction "GND_39") (pintype "passive"))
    )
    (net (code "136") (name "unconnected-(U2-GND-Pad45)") (class "Default")
      (node (ref "U2") (pin "45") (pinfunction "GND_45") (pintype "passive"))
    )
    (net (code "137") (name "unconnected-(U2-GND-Pad46)") (class "Default")
      (node (ref "U2") (pin "46") (pinfunction "GND_46") (pintype "passive"))
    )
    (net (code "138") (name "unconnected-(U2-GND-Pad53)") (class "Default")
      (node (ref "U2") (pin "53") (pinfunction "GND_53") (pintype "passive"))
    )
    (net (code "139") (name "unconnected-(U2-GND-Pad54)") (class "Default")
      (node (ref "U2") (pin "54") (pinfunction "GND_54") (pintype "passive"))
    )
    (net (code "140") (name "unconnected-(U2-GND-Pad58)") (class "Default")
      (node (ref "U2") (pin "58") (pinfunction "GND_58") (pintype "passive"))
    )
    (net (code "141") (name "unconnected-(U2-GND-Pad59)") (class "Default")
      (node (ref "U2") (pin "59") (pinfunction "GND_59") (pintype "passive"))
    )
    (net (code "142") (name "unconnected-(U2-GND-Pad61)") (class "Default")
      (node (ref "U2") (pin "61") (pinfunction "GND_61") (pintype "passive"))
    )
    (net (code "143") (name "unconnected-(U2-GND-Pad62)") (class "Default")
      (node (ref "U2") (pin "62") (pinfunction "GND_62") (pintype "passive"))
    )
    (net (code "144") (name "unconnected-(U2-GND-Pad63)") (class "Default")
      (node (ref "U2") (pin "63") (pinfunction "GND_63") (pintype "passive"))
    )
    (net (code "145") (name "unconnected-(U2-GND-Pad64)") (class "Default")
      (node (ref "U2") (pin "64") (pinfunction "GND_64") (pintype "passive"))
    )
    (net (code "146") (name "unconnected-(U2-GND-Pad65)") (class "Default")
      (node (ref "U2") (pin "65") (pinfunction "GND_65") (pintype "passive"))
    )
    (net (code "147") (name "unconnected-(U2-GPIO1{slash}KBR4-Pad40)") (class "Default")
      (node (ref "U2") (pin "40") (pinfunction "GPIO1/KBR4_40") (pintype "passive"))
    )
    (net (code "148") (name "unconnected-(U2-GPIO2{slash}KBR3-Pad41)") (class "Default")
      (node (ref "U2") (pin "41") (pinfunction "GPIO2/KBR3_41") (pintype "passive"))
    )
    (net (code "149") (name "unconnected-(U2-GPIO3{slash}KBR2-Pad42)") (class "Default")
      (node (ref "U2") (pin "42") (pinfunction "GPIO3/KBR2_42") (pintype "passive"))
    )
    (net (code "150") (name "unconnected-(U2-GPIO4{slash}KBR1-Pad43)") (class "Default")
      (node (ref "U2") (pin "43") (pinfunction "GPIO4/KBR1_43") (pintype "passive"))
    )
    (net (code "151") (name "unconnected-(U2-GPIO5{slash}KBR0-Pad44)") (class "Default")
      (node (ref "U2") (pin "44") (pinfunction "GPIO5/KBR0_44") (pintype "passive"))
    )
    (net (code "152") (name "unconnected-(U2-GPIO6{slash}KBC4-Pad47)") (class "Default")
      (node (ref "U2") (pin "47") (pinfunction "GPIO6/KBC4_47") (pintype "passive"))
    )
    (net (code "153") (name "unconnected-(U2-GPIO7{slash}KBC3-Pad48)") (class "Default")
      (node (ref "U2") (pin "48") (pinfunction "GPIO7/KBC3_48") (pintype "passive"))
    )
    (net (code "154") (name "unconnected-(U2-GPIO8{slash}KBC2-Pad49)") (class "Default")
      (node (ref "U2") (pin "49") (pinfunction "GPIO8/KBC2_49") (pintype "passive"))
    )
    (net (code "155") (name "unconnected-(U2-GPIO9{slash}KBC1-Pad50)") (class "Default")
      (node (ref "U2") (pin "50") (pinfunction "GPIO9/KBC1_50") (pintype "passive"))
    )
    (net (code "156") (name "unconnected-(U2-GPIO10{slash}KBC0-Pad51)") (class "Default")
      (node (ref "U2") (pin "51") (pinfunction "GPIO10/KBC0_51") (pintype "passive"))
    )
    (net (code "157") (name "unconnected-(U2-GPIO11-Pad67)") (class "Default")
      (node (ref "U2") (pin "67") (pinfunction "GPIO11_67") (pintype "passive"))
    )
    (net (code "158") (name "unconnected-(U2-GPIO12-Pad68)") (class "Default")
      (node (ref "U2") (pin "68") (pinfunction "GPIO12_68") (pintype "passive"))
    )
    (net (code "159") (name "unconnected-(U2-LINEIN_L-Pad24)") (class "Default")
      (node (ref "U2") (pin "24") (pinfunction "LINEIN_L_24") (pintype "passive"))
    )
    (net (code "160") (name "unconnected-(U2-LINEIN_R-Pad23)") (class "Default")
      (node (ref "U2") (pin "23") (pinfunction "LINEIN_R_23") (pintype "passive"))
    )
    (net (code "161") (name "unconnected-(U2-MIC_N-Pad20)") (class "Default")
      (node (ref "U2") (pin "20") (pinfunction "MIC_N_20") (pintype "passive"))
    )
    (net (code "162") (name "unconnected-(U2-MIC_P-Pad19)") (class "Default")
      (node (ref "U2") (pin "19") (pinfunction "MIC_P_19") (pintype "passive"))
    )
    (net (code "163") (name "unconnected-(U2-N_LIGHT-Pad52)") (class "Default")
      (node (ref "U2") (pin "52") (pinfunction "N_LIGHT_52") (pintype "passive"))
    )
    (net (code "164") (name "unconnected-(U2-PWM1-Pad35)") (class "Default")
      (node (ref "U2") (pin "35") (pinfunction "PWM1_35") (pintype "passive"))
    )
    (net (code "165") (name "unconnected-(U2-PWM2-Pad36)") (class "Default")
      (node (ref "U2") (pin "36") (pinfunction "PWM2_36") (pintype "passive"))
    )
    (net (code "166") (name "unconnected-(U2-PWRKEY-Pad1)") (class "Default")
      (node (ref "U2") (pin "1") (pinfunction "PWRKEY_1") (pintype "passive"))
    )
    (net (code "167") (name "unconnected-(U2-PWRKEY_OUT-Pad2)") (class "Default")
      (node (ref "U2") (pin "2") (pinfunction "PWRKEY_OUT_2") (pintype "passive"))
    )
    (net (code "168") (name "unconnected-(U2-RF_ANT-Pad60)") (class "Default")
      (node (ref "U2") (pin "60") (pinfunction "RF_ANT_60") (pintype "passive"))
    )
    (net (code "169") (name "unconnected-(U2-RI-Pad4)") (class "Default")
      (node (ref "U2") (pin "4") (pinfunction "RI_4") (pintype "passive"))
    )
    (net (code "170") (name "unconnected-(U2-RTS-Pad8)") (class "Default")
      (node (ref "U2") (pin "8") (pinfunction "RTS_8") (pintype "passive"))
    )
    (net (code "171") (name "unconnected-(U2-RXD-Pad10)") (class "Default")
      (node (ref "U2") (pin "10") (pinfunction "RXD_10") (pintype "passive"))
    )
    (net (code "172") (name "unconnected-(U2-SCL-Pad38)") (class "Default")
      (node (ref "U2") (pin "38") (pinfunction "SCL_38") (pintype "passive"))
    )
    (net (code "173") (name "unconnected-(U2-SDA-Pad37)") (class "Default")
      (node (ref "U2") (pin "37") (pinfunction "SDA_37") (pintype "passive"))
    )
    (net (code "174") (name "unconnected-(U2-SIM_CLK-Pad32)") (class "Default")
      (node (ref "U2") (pin "32") (pinfunction "SIM_CLK_32") (pintype "passive"))
    )
    (net (code "175") (name "unconnected-(U2-SIM_DATA-Pad31)") (class "Default")
      (node (ref "U2") (pin "31") (pinfunction "SIM_DATA_31") (pintype "passive"))
    )
    (net (code "176") (name "unconnected-(U2-SIM_PRESENCE-Pad34)") (class "Default")
      (node (ref "U2") (pin "34") (pinfunction "SIM_PRESENCE_34") (pintype "passive"))
    )
    (net (code "177") (name "unconnected-(U2-SIM_RST-Pad33)") (class "Default")
      (node (ref "U2") (pin "33") (pinfunction "SIM_RST_33") (pintype "passive"))
    )
    (net (code "178") (name "unconnected-(U2-SIM_VDD-Pad30)") (class "Default")
      (node (ref "U2") (pin "30") (pinfunction "SIM_VDD_30") (pintype "passive"))
    )
    (net (code "179") (name "unconnected-(U2-SPK_N-Pad22)") (class "Default")
      (node (ref "U2") (pin "22") (pinfunction "SPK_N_22") (pintype "passive"))
    )
    (net (code "180") (name "unconnected-(U2-SPK_P-Pad21)") (class "Default")
      (node (ref "U2") (pin "21") (pinfunction "SPK_P_21") (pintype "passive"))
    )
    (net (code "181") (name "unconnected-(U2-STATUS-Pad66)") (class "Default")
      (node (ref "U2") (pin "66") (pinfunction "STATUS_66") (pintype "passive"))
    )
    (net (code "182") (name "unconnected-(U2-TXD-Pad9)") (class "Default")
      (node (ref "U2") (pin "9") (pinfunction "TXD_9") (pintype "passive"))
    )
    (net (code "183") (name "unconnected-(U2-VBAT-Pad55)") (class "Default")
      (node (ref "U2") (pin "55") (pinfunction "VBAT_55") (pintype "passive"))
    )
    (net (code "184") (name "unconnected-(U2-VBAT-Pad56)") (class "Default")
      (node (ref "U2") (pin "56") (pinfunction "VBAT_56") (pintype "passive"))
    )
    (net (code "185") (name "unconnected-(U2-VBAT-Pad57)") (class "Default")
      (node (ref "U2") (pin "57") (pinfunction "VBAT_57") (pintype "passive"))
    )
    (net (code "186") (name "unconnected-(U2-VDD_EXT-Pad15)") (class "Default")
      (node (ref "U2") (pin "15") (pinfunction "VDD_EXT_15") (pintype "passive"))
    )
    (net (code "187") (name "unconnected-(U2-VRTC-Pad26)") (class "Default")
      (node (ref "U2") (pin "26") (pinfunction "VRTC_26") (pintype "passive"))
    )
    (net (code "188") (name "unconnected-(U2-~{RESET}-Pad16)") (class "Default")
      (node (ref "U2") (pin "16") (pinfunction "~{RESET}_16") (pintype "passive"))
    )
    (net (code "189") (name "unconnected-(VBAT-Pad1)") (class "Default")
      (node (ref "VBAT") (pin "1") (pinfunction "1_1") (pintype "passive"))
    )
    (net (code "190") (name "unconnected-(VBAT-Pad2)") (class "Default")
      (node (ref "VBAT") (pin "2") (pinfunction "2_2") (pintype "passive"))
    )
  )
)
